# LDO.net
KiCad netlist of a schematic drawn in Altium Designer
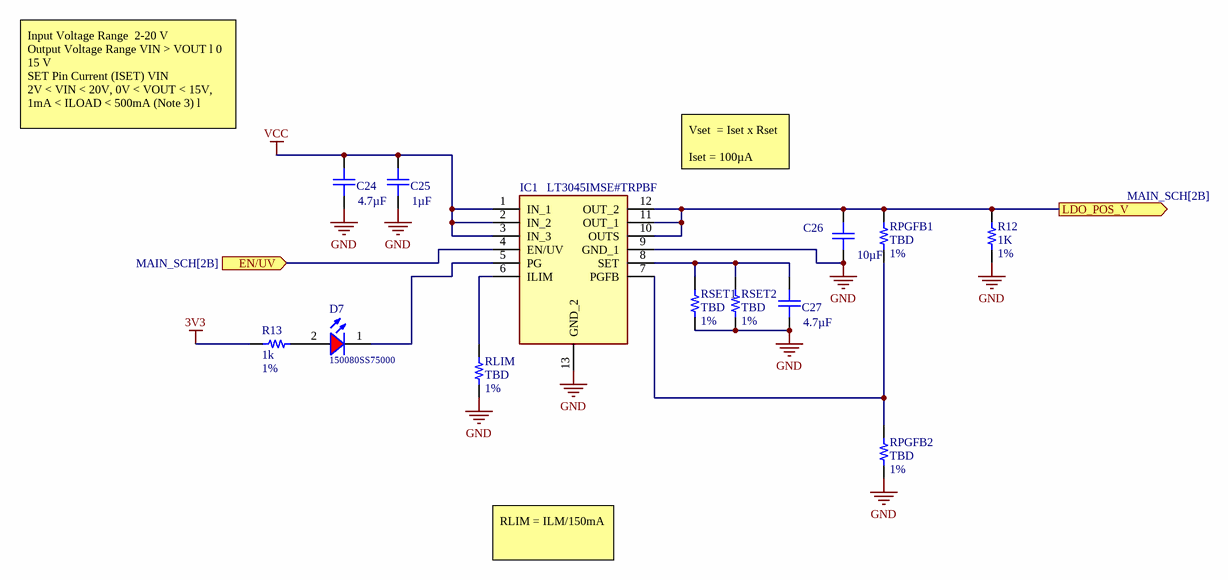
[diagram p0: LDO.SchDoc]

(export (version "E")
  (design (tool "Eeschema 10.0.6"))
  (components
    (comp (ref "C24")
      (value "4.7µF")
      (footprint "FP-CL10-IPC_B")
      (description "SMT Capacitor")
      (fields (field (name "Comment") "Capacitor"))
      (libsource (lib "ILH") (part "Capacitor"))
    )
    (comp (ref "C25")
      (value "1µF")
      (footprint "FP-CL10-IPC_B")
      (description "SMT Capacitor")
      (fields (field (name "Comment") "Capacitor"))
      (libsource (lib "ILH") (part "Capacitor"))
    )
    (comp (ref "C26")
      (value "10µF")
      (footprint "FP-CL10-IPC_B")
      (description "SMT Capacitor")
      (fields (field (name "Comment") "Capacitor"))
      (libsource (lib "ILH") (part "Capacitor"))
    )
    (comp (ref "C27")
      (value "4.7µF")
      (footprint "FP-CL10-IPC_B")
      (description "SMT Capacitor")
      (fields (field (name "Comment") "Capacitor"))
      (libsource (lib "ILH") (part "Capacitor"))
    )
    (comp (ref "D7")
      (value "150080SS75000")
      (footprint "WL-SMCW_0805")
      (description "WL-SMCW SMT Mono-color Chip LED Waterclear, size 0805, Super Red, 1.9V, 140deg")
      (fields (field (name "PUBLISHER") "Wurth Elektronik"))
      (libsource (lib "ILH") (part "LED RED"))
    )
    (comp (ref "IC1")
      (value "LT3045IMSE#TRPBF")
      (footprint "SOP65P490X110-13N")
      (description "LDO Voltage Regulators 20V, 500mA, Ultralow Noise, Ultrahigh PSRR Linear Regulator")
      (fields (field (name "MOUSER PART NUMBER") "584-LT3045IMSE#TRPBF"))
      (libsource (lib "LT3045IMSE#TRPBF") (part "LT3045IMSE#TRPBF"))
    )
    (comp (ref "R12")
      (value "1K")
      (footprint "RESC1608X06N 0603 Medium Density")
      (description "RES SMD 1K OHM 1% 1/10W 0603")
      (fields
        (field (name "TOLERANCE") "1%")
        (field (name "JLCPCB PART #") "C21190")
        (field (name "POWER") "100mW")
      )
      (libsource (lib "ILH") (part "Resistor Tolerance"))
    )
    (comp (ref "R13")
      (value "1k")
      (footprint "RESC1608X06N 0603 Medium Density")
      (description "RES SMD 1K OHM 1% 1/10W 0603")
      (fields
        (field (name "TOLERANCE") "1%")
        (field (name "JLCPCB PART #") "C21190")
        (field (name "POWER") "100mW")
      )
      (libsource (lib "ILH") (part "Resistor Tolerance"))
    )
    (comp (ref "RLIM")
      (value "TBD")
      (footprint "RESC1608X06N 0603 Medium Density")
      (description "RES SMD 1K OHM 1% 1/10W 0603")
      (fields
        (field (name "TOLERANCE") "1%")
        (field (name "JLCPCB PART #") "C21190")
        (field (name "POWER") "100mW")
      )
      (libsource (lib "ILH") (part "Resistor Tolerance"))
    )
    (comp (ref "RPGFB1")
      (value "TBD")
      (footprint "RESC1608X06N 0603 Medium Density")
      (description "RES SMD 1K OHM 1% 1/10W 0603")
      (fields
        (field (name "TOLERANCE") "1%")
        (field (name "JLCPCB PART #") "C21190")
        (field (name "POWER") "100mW")
      )
      (libsource (lib "ILH") (part "Resistor Tolerance"))
    )
    (comp (ref "RPGFB2")
      (value "TBD")
      (footprint "RESC1608X06N 0603 Medium Density")
      (description "RES SMD 1K OHM 1% 1/10W 0603")
      (fields
        (field (name "TOLERANCE") "1%")
        (field (name "JLCPCB PART #") "C21190")
        (field (name "POWER") "100mW")
      )
      (libsource (lib "ILH") (part "Resistor Tolerance"))
    )
    (comp (ref "RSET1")
      (value "TBD")
      (footprint "RESC1608X06N 0603 Medium Density")
      (description "RES SMD 1K OHM 1% 1/10W 0603")
      (fields
        (field (name "TOLERANCE") "1%")
        (field (name "JLCPCB PART #") "C21190")
        (field (name "POWER") "100mW")
      )
      (libsource (lib "ILH") (part "Resistor Tolerance"))
    )
    (comp (ref "RSET2")
      (value "TBD")
      (footprint "RESC1608X06N 0603 Medium Density")
      (description "RES SMD 1K OHM 1% 1/10W 0603")
      (fields
        (field (name "TOLERANCE") "1%")
        (field (name "JLCPCB PART #") "C21190")
        (field (name "POWER") "100mW")
      )
      (libsource (lib "ILH") (part "Resistor Tolerance"))
    )
  )
  (nets
    (net (code "1") (name "/EN{slash}UV") (class "Default")
      (node (ref "IC1") (pin "4") (pinfunction "EN/UV_4") (pintype "passive"))
    )
    (net (code "2") (name "/LDO_POS_V") (class "Default")
      (node (ref "C26") (pin "2") (pinfunction "2_2") (pintype "passive"))
      (node (ref "IC1") (pin "10") (pinfunction "OUTS_10") (pintype "passive"))
      (node (ref "IC1") (pin "11") (pinfunction "OUT_1_11") (pintype "passive"))
      (node (ref "IC1") (pin "12") (pinfunction "OUT_2_12") (pintype "passive"))
      (node (ref "R12") (pin "1") (pinfunction "1_1") (pintype "passive"))
      (node (ref "RPGFB1") (pin "1") (pinfunction "1_1") (pintype "passive"))
    )
    (net (code "3") (name "3V3") (class "Default")
      (node (ref "R13") (pin "2") (pinfunction "2_2") (pintype "passive"))
    )
    (net (code "4") (name "GND") (class "Default")
      (node (ref "C24") (pin "1") (pinfunction "1_1") (pintype "passive"))
      (node (ref "C25") (pin "1") (pinfunction "1_1") (pintype "passive"))
      (node (ref "C26") (pin "1") (pinfunction "1_1") (pintype "passive"))
      (node (ref "C27") (pin "1") (pinfunction "1_1") (pintype "passive"))
      (node (ref "IC1") (pin "13") (pinfunction "GND_2_13") (pintype "passive"))
      (node (ref "IC1") (pin "9") (pinfunction "GND_1_9") (pintype "passive"))
      (node (ref "R12") (pin "2") (pinfunction "2_2") (pintype "passive"))
      (node (ref "RLIM") (pin "2") (pinfunction "2_2") (pintype "passive"))
      (node (ref "RPGFB2") (pin "2") (pinfunction "2_2") (pintype "passive"))
      (node (ref "RSET1") (pin "2") (pinfunction "2_2") (pintype "passive"))
      (node (ref "RSET2") (pin "2") (pinfunction "2_2") (pintype "passive"))
    )
    (net (code "5") (name "Net-(D7-A)") (class "Default")
      (node (ref "D7") (pin "2") (pinfunction "A_2") (pintype "passive"))
      (node (ref "R13") (pin "1") (pinfunction "1_1") (pintype "passive"))
    )
    (net (code "6") (name "Net-(D7-K)") (class "Default")
      (node (ref "D7") (pin "1") (pinfunction "K_1") (pintype "passive"))
      (node (ref "IC1") (pin "5") (pinfunction "PG_5") (pintype "passive"))
    )
    (net (code "7") (name "Net-(IC1-ILIM)") (class "Default")
      (node (ref "IC1") (pin "6") (pinfunction "ILIM_6") (pintype "passive"))
      (node (ref "RLIM") (pin "1") (pinfunction "1_1") (pintype "passive"))
    )
    (net (code "8") (name "Net-(IC1-PGFB)") (class "Default")
      (node (ref "IC1") (pin "7") (pinfunction "PGFB_7") (pintype "passive"))
      (node (ref "RPGFB1") (pin "2") (pinfunction "2_2") (pintype "passive"))
      (node (ref "RPGFB2") (pin "1") (pinfunction "1_1") (pintype "passive"))
    )
    (net (code "9") (name "Net-(IC1-SET)") (class "Default")
      (node (ref "C27") (pin "2") (pinfunction "2_2") (pintype "passive"))
      (node (ref "IC1") (pin "8") (pinfunction "SET_8") (pintype "passive"))
      (node (ref "RSET1") (pin "1") (pinfunction "1_1") (pintype "passive"))
      (node (ref "RSET2") (pin "1") (pinfunction "1_1") (pintype "passive"))
    )
    (net (code "10") (name "VCC") (class "Default")
      (node (ref "C24") (pin "2") (pinfunction "2_2") (pintype "passive"))
      (node (ref "C25") (pin "2") (pinfunction "2_2") (pintype "passive"))
      (node (ref "IC1") (pin "1") (pinfunction "IN_1_1") (pintype "passive"))
      (node (ref "IC1") (pin "2") (pinfunction "IN_2_2") (pintype "passive"))
      (node (ref "IC1") (pin "3") (pinfunction "IN_3_3") (pintype "passive"))
    )
  )
)
